# arduinoshield.net
KiCad netlist of a schematic drawn in EAGLE
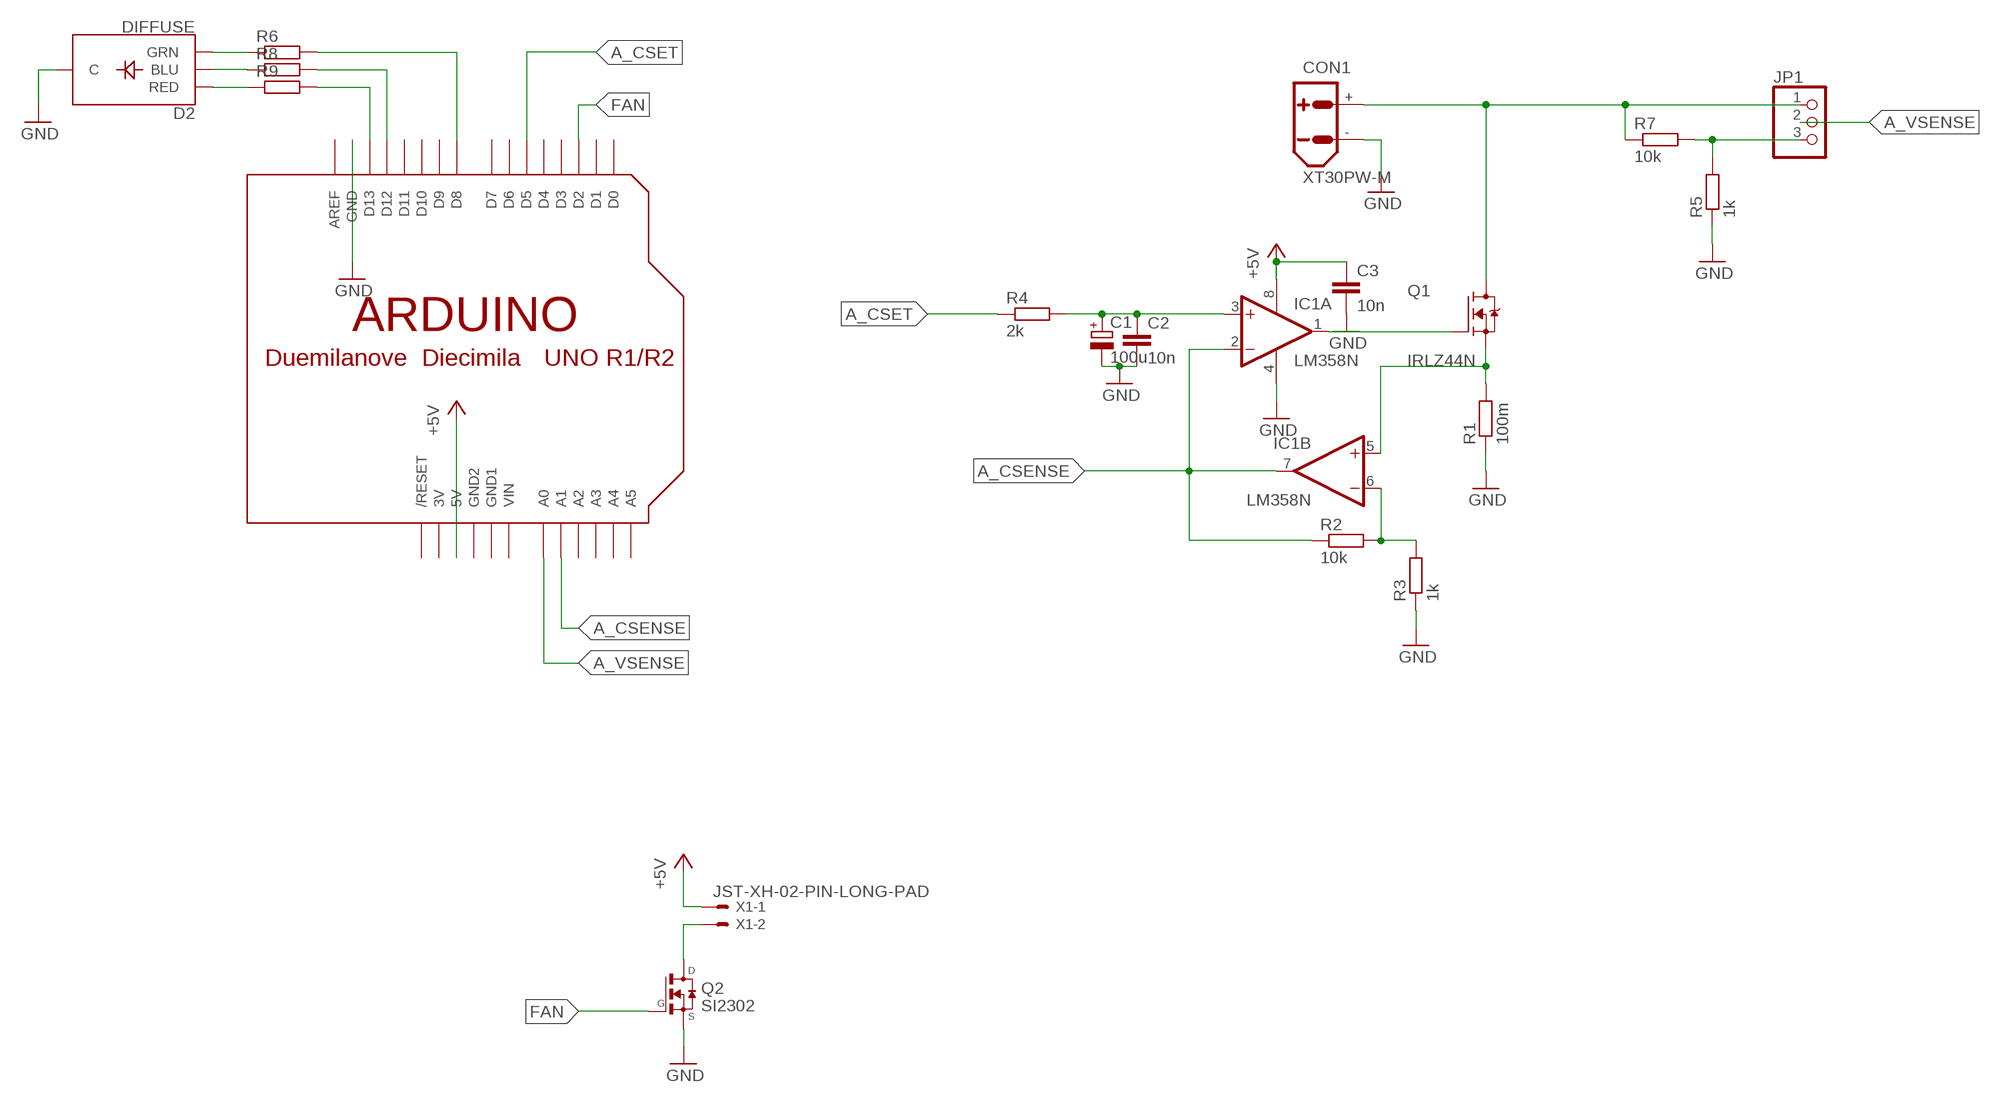
[diagram p0: schematic, sheet 1]

(export (version "E")
  (design (tool "Eeschema 10.0.6"))
  (components
    (comp (ref "C1")
      (value "100u")
      (footprint "eagle-import:E2,5-7")
      (libsource (lib "eagle-import") (part "CPOL-EUE2.5-7"))
    )
    (comp (ref "C2")
      (value "10n")
      (footprint "eagle-import:C050-025X075")
      (libsource (lib "eagle-import") (part "C-EU050-025X075"))
    )
    (comp (ref "C3")
      (value "10n")
      (footprint "eagle-import:C050-025X075")
      (libsource (lib "eagle-import") (part "C-EU050-025X075"))
    )
    (comp (ref "CON1")
      (value "XT30PW-M")
      (footprint "eagle-import:XT30PW-M")
      (libsource (lib "eagle-import") (part "XT30PW-M"))
    )
    (comp (ref "D2")
      (value "DIFFUSE")
      (footprint "eagle-import:LED-RGB-THRU")
      (libsource (lib "eagle-import") (part "LED-RGB-CCDIFFUSE"))
    )
    (comp (ref "IC1")
      (value "LM358N")
      (footprint "eagle-import:DIL08")
      (libsource (lib "eagle-import") (part "LM358N"))
    )
    (comp (ref "JP1")
      (value "PINHD-1X3")
      (footprint "eagle-import:1X03")
      (libsource (lib "eagle-import") (part "PINHD-1X3"))
    )
    (comp (ref "Q1")
      (value "IRLZ44N")
      (footprint "eagle-import:TO254P1054X469X1930-3")
      (fields (field (name "MF") "Infineon Technologies"))
      (libsource (lib "eagle-import") (part "IRLZ44N"))
    )
    (comp (ref "Q2")
      (value "SI2302")
      (footprint "eagle-import:SOT23")
      (fields (field (name "MF") "Vishay Siliconix"))
      (libsource (lib "eagle-import") (part "SI2302"))
    )
    (comp (ref "R1")
      (value "100m")
      (footprint "eagle-import:R2512")
      (libsource (lib "eagle-import") (part "R-EU_R2512"))
    )
    (comp (ref "R2")
      (value "10k")
      (footprint "eagle-import:M1206")
      (libsource (lib "eagle-import") (part "R-EU_M1206"))
    )
    (comp (ref "R3")
      (value "1k")
      (footprint "eagle-import:M1206")
      (libsource (lib "eagle-import") (part "R-EU_M1206"))
    )
    (comp (ref "R4")
      (value "2k")
      (footprint "eagle-import:M1206")
      (libsource (lib "eagle-import") (part "R-EU_M1206"))
    )
    (comp (ref "R5")
      (value "1k")
      (footprint "eagle-import:M1206")
      (libsource (lib "eagle-import") (part "R-EU_M1206"))
    )
    (comp (ref "R6")
      (value "R-EU_M1206")
      (footprint "eagle-import:M1206")
      (libsource (lib "eagle-import") (part "R-EU_M1206"))
    )
    (comp (ref "R7")
      (value "10k")
      (footprint "eagle-import:M1206")
      (libsource (lib "eagle-import") (part "R-EU_M1206"))
    )
    (comp (ref "R8")
      (value "R-EU_M1206")
      (footprint "eagle-import:M1206")
      (libsource (lib "eagle-import") (part "R-EU_M1206"))
    )
    (comp (ref "R9")
      (value "R-EU_M1206")
      (footprint "eagle-import:M1206")
      (libsource (lib "eagle-import") (part "R-EU_M1206"))
    )
    (comp (ref "U$2")
      (value "ARDUINO-NOHOLE")
      (footprint "eagle-import:ARDUINO-NOHOLE")
      (libsource (lib "eagle-import") (part "ARDUINO-NOHOLE"))
    )
    (comp (ref "X1")
      (value "JST-XH-02-PIN-LONG-PAD")
      (footprint "eagle-import:JST-XH-02-PACKAGE-LONG-PAD")
      (libsource (lib "eagle-import") (part "JST-XH-02-PIN-LONG-PAD"))
    )
  )
  (nets
    (net (code "1") (name "+5V") (class "Default")
      (node (ref "C3") (pin "1") (pinfunction "1_1") (pintype "passive"))
      (node (ref "IC1") (pin "8") (pinfunction "V+_8") (pintype "power_in"))
      (node (ref "U$2") (pin "5V") (pinfunction "5V_5V") (pintype "power_in"))
      (node (ref "X1") (pin "1") (pinfunction "S_1") (pintype "passive"))
    )
    (net (code "2") (name "/3V") (class "Default")
      (node (ref "U$2") (pin "3V") (pinfunction "3V_3V") (pintype "power_in"))
    )
    (net (code "3") (name "/GND1") (class "Default")
      (node (ref "U$2") (pin "GND1") (pinfunction "GND1_GND1") (pintype "power_in"))
    )
    (net (code "4") (name "/GND2") (class "Default")
      (node (ref "U$2") (pin "GND2") (pinfunction "GND2_GND2") (pintype "power_in"))
    )
    (net (code "5") (name "/VIN") (class "Default")
      (node (ref "U$2") (pin "VIN") (pinfunction "VIN_VIN") (pintype "power_in"))
    )
    (net (code "6") (name "A_CSENSE") (class "Default")
      (node (ref "IC1") (pin "2") (pinfunction "-IN_2") (pintype "input"))
      (node (ref "IC1") (pin "7") (pinfunction "OUT_7") (pintype "output"))
      (node (ref "R2") (pin "1") (pinfunction "1_1") (pintype "passive"))
      (node (ref "U$2") (pin "A1") (pinfunction "A1_A1") (pintype "bidirectional"))
    )
    (net (code "7") (name "A_CSET") (class "Default")
      (node (ref "R4") (pin "1") (pinfunction "1_1") (pintype "passive"))
      (node (ref "U$2") (pin "D5") (pinfunction "D5_D5") (pintype "bidirectional"))
    )
    (net (code "8") (name "A_VSENSE") (class "Default")
      (node (ref "JP1") (pin "2") (pinfunction "2_2") (pintype "passive"))
      (node (ref "U$2") (pin "A0") (pinfunction "A0_A0") (pintype "bidirectional"))
    )
    (net (code "9") (name "FAN") (class "Default")
      (node (ref "Q2") (pin "1") (pinfunction "G_1") (pintype "passive"))
      (node (ref "U$2") (pin "D2") (pinfunction "D2_D2") (pintype "bidirectional"))
    )
    (net (code "10") (name "GND") (class "Default")
      (node (ref "C1") (pin "-") (pinfunction "-_-") (pintype "passive"))
      (node (ref "C2") (pin "2") (pinfunction "2_2") (pintype "passive"))
      (node (ref "C3") (pin "2") (pinfunction "2_2") (pintype "passive"))
      (node (ref "CON1") (pin "-") (pinfunction "-_-") (pintype "power_in"))
      (node (ref "D2") (pin "2") (pinfunction "C_2") (pintype "bidirectional"))
      (node (ref "IC1") (pin "4") (pinfunction "V-_4") (pintype "power_in"))
      (node (ref "Q2") (pin "2") (pinfunction "S_2") (pintype "passive"))
      (node (ref "R1") (pin "1") (pinfunction "1_1") (pintype "passive"))
      (node (ref "R3") (pin "1") (pinfunction "1_1") (pintype "passive"))
      (node (ref "R5") (pin "1") (pinfunction "1_1") (pintype "passive"))
      (node (ref "U$2") (pin "GND") (pinfunction "GND_GND") (pintype "power_in"))
    )
    (net (code "11") (name "Net-(D2-BLU)") (class "Default")
      (node (ref "D2") (pin "4") (pinfunction "BLU_4") (pintype "bidirectional"))
      (node (ref "R8") (pin "1") (pinfunction "1_1") (pintype "passive"))
    )
    (net (code "12") (name "Net-(D2-GRN)") (class "Default")
      (node (ref "D2") (pin "3") (pinfunction "GRN_3") (pintype "bidirectional"))
      (node (ref "R6") (pin "1") (pinfunction "1_1") (pintype "passive"))
    )
    (net (code "13") (name "Net-(D2-RED)") (class "Default")
      (node (ref "D2") (pin "1") (pinfunction "RED_1") (pintype "bidirectional"))
      (node (ref "R9") (pin "1") (pinfunction "1_1") (pintype "passive"))
    )
    (net (code "14") (name "Net-(IC1A-+IN)") (class "Default")
      (node (ref "C1") (pin "+") (pinfunction "+_+") (pintype "passive"))
      (node (ref "C2") (pin "1") (pinfunction "1_1") (pintype "passive"))
      (node (ref "IC1") (pin "3") (pinfunction "+IN_3") (pintype "input"))
      (node (ref "R4") (pin "2") (pinfunction "2_2") (pintype "passive"))
    )
    (net (code "15") (name "Net-(IC1A-OUT)") (class "Default")
      (node (ref "IC1") (pin "1") (pinfunction "OUT_1") (pintype "output"))
      (node (ref "Q1") (pin "1") (pinfunction "G_1") (pintype "passive"))
    )
    (net (code "16") (name "Net-(IC1B-+IN)") (class "Default")
      (node (ref "IC1") (pin "5") (pinfunction "+IN_5") (pintype "input"))
      (node (ref "Q1") (pin "3") (pinfunction "S_3") (pintype "passive"))
      (node (ref "R1") (pin "2") (pinfunction "2_2") (pintype "passive"))
    )
    (net (code "17") (name "Net-(IC1B--IN)") (class "Default")
      (node (ref "IC1") (pin "6") (pinfunction "-IN_6") (pintype "input"))
      (node (ref "R2") (pin "2") (pinfunction "2_2") (pintype "passive"))
      (node (ref "R3") (pin "2") (pinfunction "2_2") (pintype "passive"))
    )
    (net (code "18") (name "Net-(JP1-Pad3)") (class "Default")
      (node (ref "JP1") (pin "3") (pinfunction "3_3") (pintype "passive"))
      (node (ref "R5") (pin "2") (pinfunction "2_2") (pintype "passive"))
      (node (ref "R7") (pin "2") (pinfunction "2_2") (pintype "passive"))
    )
    (net (code "19") (name "Net-(Q1-D)") (class "Default")
      (node (ref "CON1") (pin "+") (pinfunction "+_+") (pintype "power_in"))
      (node (ref "JP1") (pin "1") (pinfunction "1_1") (pintype "passive"))
      (node (ref "Q1") (pin "2") (pinfunction "D_2") (pintype "passive"))
      (node (ref "R7") (pin "1") (pinfunction "1_1") (pintype "passive"))
    )
    (net (code "20") (name "Net-(Q2-D)") (class "Default")
      (node (ref "Q2") (pin "3") (pinfunction "D_3") (pintype "passive"))
      (node (ref "X1") (pin "2") (pinfunction "S_2") (pintype "passive"))
    )
    (net (code "21") (name "Net-(R6-Pad2)") (class "Default")
      (node (ref "R6") (pin "2") (pinfunction "2_2") (pintype "passive"))
      (node (ref "U$2") (pin "D8") (pinfunction "D8_D8") (pintype "bidirectional"))
    )
    (net (code "22") (name "Net-(R8-Pad2)") (class "Default")
      (node (ref "R8") (pin "2") (pinfunction "2_2") (pintype "passive"))
      (node (ref "U$2") (pin "D12") (pinfunction "D12_D12") (pintype "bidirectional"))
    )
    (net (code "23") (name "Net-(R9-Pad2)") (class "Default")
      (node (ref "R9") (pin "2") (pinfunction "2_2") (pintype "passive"))
      (node (ref "U$2") (pin "D13") (pinfunction "D13_D13") (pintype "bidirectional"))
    )
    (net (code "24") (name "unconnected-(U$2-PadA2)") (class "Default")
      (node (ref "U$2") (pin "A2") (pinfunction "A2_A2") (pintype "bidirectional"))
    )
    (net (code "25") (name "unconnected-(U$2-PadA3)") (class "Default")
      (node (ref "U$2") (pin "A3") (pinfunction "A3_A3") (pintype "bidirectional"))
    )
    (net (code "26") (name "unconnected-(U$2-PadA4)") (class "Default")
      (node (ref "U$2") (pin "A4") (pinfunction "A4_A4") (pintype "bidirectional"))
    )
    (net (code "27") (name "unconnected-(U$2-PadA5)") (class "Default")
      (node (ref "U$2") (pin "A5") (pinfunction "A5_A5") (pintype "bidirectional"))
    )
    (net (code "28") (name "unconnected-(U$2-PadAREF)") (class "Default")
      (node (ref "U$2") (pin "AREF") (pinfunction "AREF_AREF") (pintype "bidirectional"))
    )
    (net (code "29") (name "unconnected-(U$2-PadD0)") (class "Default")
      (node (ref "U$2") (pin "D0") (pinfunction "D0_D0") (pintype "bidirectional"))
    )
    (net (code "30") (name "unconnected-(U$2-PadD1)") (class "Default")
      (node (ref "U$2") (pin "D1") (pinfunction "D1_D1") (pintype "bidirectional"))
    )
    (net (code "31") (name "unconnected-(U$2-PadD3)") (class "Default")
      (node (ref "U$2") (pin "D3") (pinfunction "D3_D3") (pintype "bidirectional"))
    )
    (net (code "32") (name "unconnected-(U$2-PadD4)") (class "Default")
      (node (ref "U$2") (pin "D4") (pinfunction "D4_D4") (pintype "bidirectional"))
    )
    (net (code "33") (name "unconnected-(U$2-PadD6)") (class "Default")
      (node (ref "U$2") (pin "D6") (pinfunction "D6_D6") (pintype "bidirectional"))
    )
    (net (code "34") (name "unconnected-(U$2-PadD7)") (class "Default")
      (node (ref "U$2") (pin "D7") (pinfunction "D7_D7") (pintype "bidirectional"))
    )
    (net (code "35") (name "unconnected-(U$2-PadD9)") (class "Default")
      (node (ref "U$2") (pin "D9") (pinfunction "D9_D9") (pintype "bidirectional"))
    )
    (net (code "36") (name "unconnected-(U$2-PadD10)") (class "Default")
      (node (ref "U$2") (pin "D10") (pinfunction "D10_D10") (pintype "bidirectional"))
    )
    (net (code "37") (name "unconnected-(U$2-PadD11)") (class "Default")
      (node (ref "U$2") (pin "D11") (pinfunction "D11_D11") (pintype "bidirectional"))
    )
    (net (code "38") (name "unconnected-(U$2-{slash}RESET-PadRESET)") (class "Default")
      (node (ref "U$2") (pin "RESET") (pinfunction "/RESET_RESET") (pintype "bidirectional"))
    )
  )
)
